# LED_Matrix.net
KiCad netlist of a schematic drawn in Altium Designer
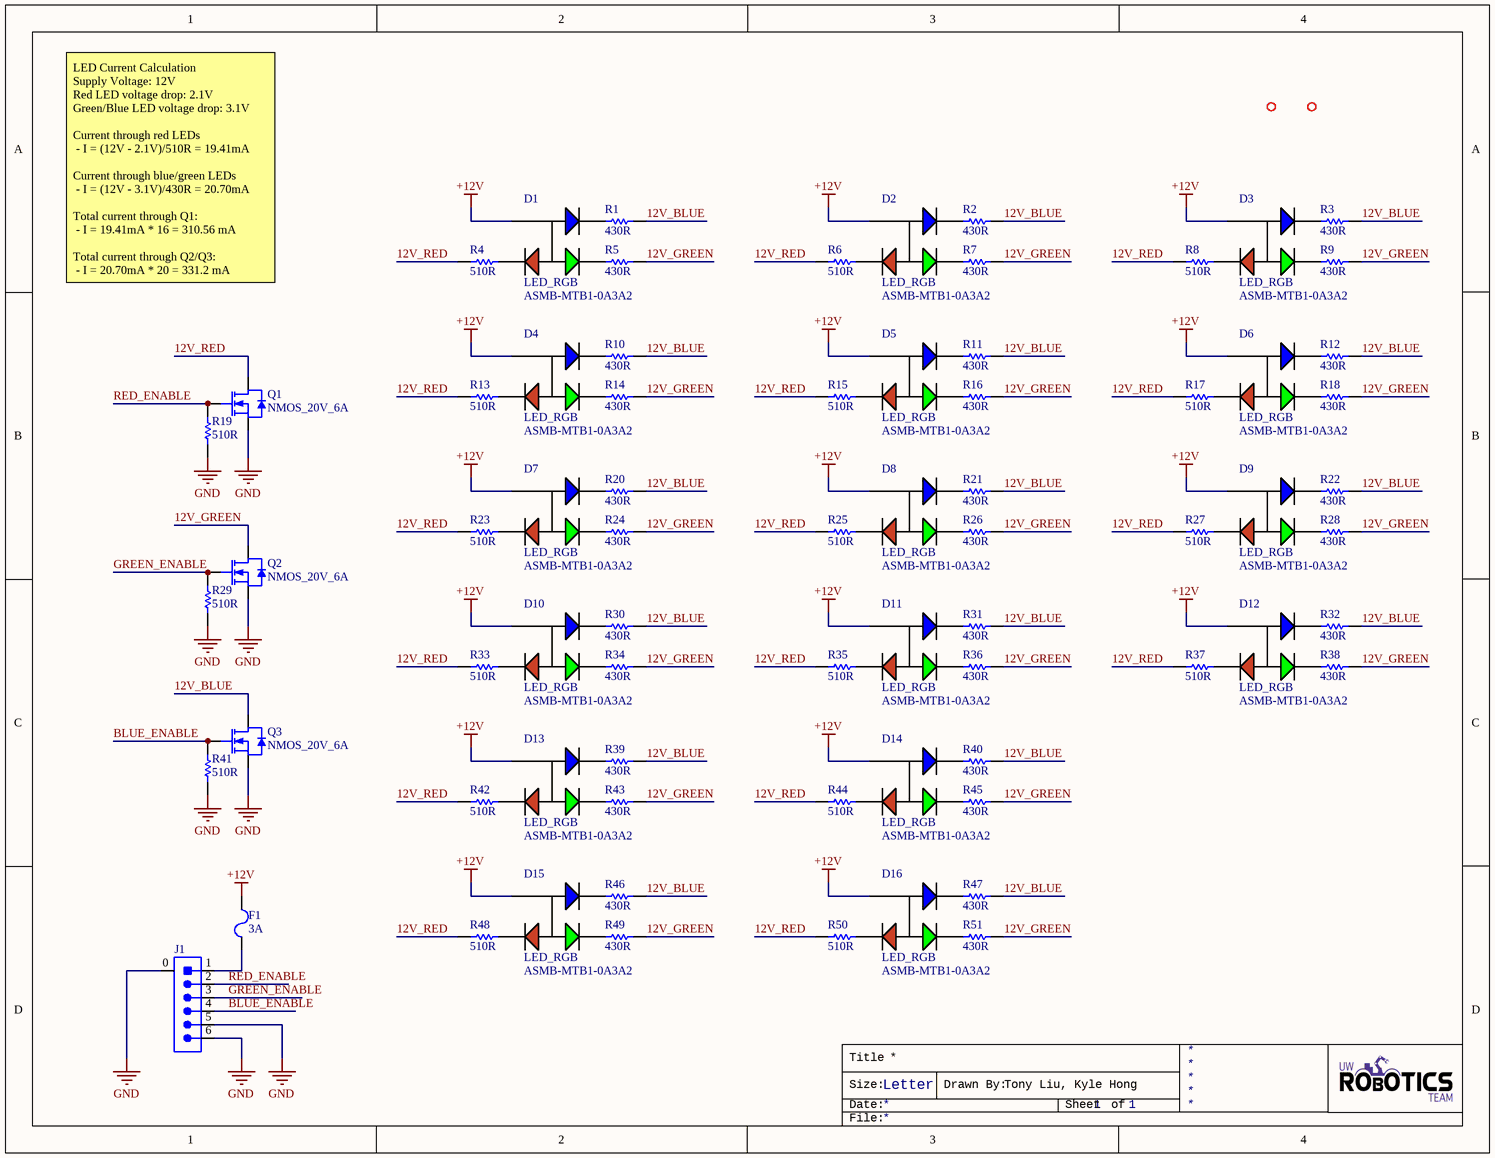
[diagram p0: LED Matrix.SchDoc]

(export (version "E")
  (design (tool "Eeschema 10.0.6"))
  (components
    (comp (ref "D1")
      (value "LED_RGB")
      (footprint "LED_RGB")
      (description "LED RGB DIFFUSED 4PLCC SMD")
      (fields (field (name "MANUFACTURER PART NUMBER 1") "ASMB-MTB1-0A3A2"))
      (libsource (lib "UWRT_Schematic_Library_2020") (part "LED_RGB"))
    )
    (comp (ref "D2")
      (value "LED_RGB")
      (footprint "LED_RGB")
      (description "LED RGB DIFFUSED 4PLCC SMD")
      (fields (field (name "MANUFACTURER PART NUMBER 1") "ASMB-MTB1-0A3A2"))
      (libsource (lib "UWRT_Schematic_Library_2020") (part "LED_RGB"))
    )
    (comp (ref "D3")
      (value "LED_RGB")
      (footprint "LED_RGB")
      (description "LED RGB DIFFUSED 4PLCC SMD")
      (fields (field (name "MANUFACTURER PART NUMBER 1") "ASMB-MTB1-0A3A2"))
      (libsource (lib "UWRT_Schematic_Library_2020") (part "LED_RGB"))
    )
    (comp (ref "D4")
      (value "LED_RGB")
      (footprint "LED_RGB")
      (description "LED RGB DIFFUSED 4PLCC SMD")
      (fields (field (name "MANUFACTURER PART NUMBER 1") "ASMB-MTB1-0A3A2"))
      (libsource (lib "UWRT_Schematic_Library_2020") (part "LED_RGB"))
    )
    (comp (ref "D5")
      (value "LED_RGB")
      (footprint "LED_RGB")
      (description "LED RGB DIFFUSED 4PLCC SMD")
      (fields (field (name "MANUFACTURER PART NUMBER 1") "ASMB-MTB1-0A3A2"))
      (libsource (lib "UWRT_Schematic_Library_2020") (part "LED_RGB"))
    )
    (comp (ref "D6")
      (value "LED_RGB")
      (footprint "LED_RGB")
      (description "LED RGB DIFFUSED 4PLCC SMD")
      (fields (field (name "MANUFACTURER PART NUMBER 1") "ASMB-MTB1-0A3A2"))
      (libsource (lib "UWRT_Schematic_Library_2020") (part "LED_RGB"))
    )
    (comp (ref "D7")
      (value "LED_RGB")
      (footprint "LED_RGB")
      (description "LED RGB DIFFUSED 4PLCC SMD")
      (fields (field (name "MANUFACTURER PART NUMBER 1") "ASMB-MTB1-0A3A2"))
      (libsource (lib "UWRT_Schematic_Library_2020") (part "LED_RGB"))
    )
    (comp (ref "D8")
      (value "LED_RGB")
      (footprint "LED_RGB")
      (description "LED RGB DIFFUSED 4PLCC SMD")
      (fields (field (name "MANUFACTURER PART NUMBER 1") "ASMB-MTB1-0A3A2"))
      (libsource (lib "UWRT_Schematic_Library_2020") (part "LED_RGB"))
    )
    (comp (ref "D9")
      (value "LED_RGB")
      (footprint "LED_RGB")
      (description "LED RGB DIFFUSED 4PLCC SMD")
      (fields (field (name "MANUFACTURER PART NUMBER 1") "ASMB-MTB1-0A3A2"))
      (libsource (lib "UWRT_Schematic_Library_2020") (part "LED_RGB"))
    )
    (comp (ref "D10")
      (value "LED_RGB")
      (footprint "LED_RGB")
      (description "LED RGB DIFFUSED 4PLCC SMD")
      (fields (field (name "MANUFACTURER PART NUMBER 1") "ASMB-MTB1-0A3A2"))
      (libsource (lib "UWRT_Schematic_Library_2020") (part "LED_RGB"))
    )
    (comp (ref "D11")
      (value "LED_RGB")
      (footprint "LED_RGB")
      (description "LED RGB DIFFUSED 4PLCC SMD")
      (fields (field (name "MANUFACTURER PART NUMBER 1") "ASMB-MTB1-0A3A2"))
      (libsource (lib "UWRT_Schematic_Library_2020") (part "LED_RGB"))
    )
    (comp (ref "D12")
      (value "LED_RGB")
      (footprint "LED_RGB")
      (description "LED RGB DIFFUSED 4PLCC SMD")
      (fields (field (name "MANUFACTURER PART NUMBER 1") "ASMB-MTB1-0A3A2"))
      (libsource (lib "UWRT_Schematic_Library_2020") (part "LED_RGB"))
    )
    (comp (ref "D13")
      (value "LED_RGB")
      (footprint "LED_RGB")
      (description "LED RGB DIFFUSED 4PLCC SMD")
      (fields (field (name "MANUFACTURER PART NUMBER 1") "ASMB-MTB1-0A3A2"))
      (libsource (lib "UWRT_Schematic_Library_2020") (part "LED_RGB"))
    )
    (comp (ref "D14")
      (value "LED_RGB")
      (footprint "LED_RGB")
      (description "LED RGB DIFFUSED 4PLCC SMD")
      (fields (field (name "MANUFACTURER PART NUMBER 1") "ASMB-MTB1-0A3A2"))
      (libsource (lib "UWRT_Schematic_Library_2020") (part "LED_RGB"))
    )
    (comp (ref "D15")
      (value "LED_RGB")
      (footprint "LED_RGB")
      (description "LED RGB DIFFUSED 4PLCC SMD")
      (fields (field (name "MANUFACTURER PART NUMBER 1") "ASMB-MTB1-0A3A2"))
      (libsource (lib "UWRT_Schematic_Library_2020") (part "LED_RGB"))
    )
    (comp (ref "D16")
      (value "LED_RGB")
      (footprint "LED_RGB")
      (description "LED RGB DIFFUSED 4PLCC SMD")
      (fields (field (name "MANUFACTURER PART NUMBER 1") "ASMB-MTB1-0A3A2"))
      (libsource (lib "UWRT_Schematic_Library_2020") (part "LED_RGB"))
    )
    (comp (ref "F1")
      (value "FUSE_3A_1206")
      (footprint "FUSE_1206")
      (description "FUSE BOARD MNT 3A 32VAC/VDC 1206")
      (fields (field (name "CURRENT RATING") "3A"))
      (libsource (lib "UWRT_Schematic_Library_2020") (part "FUSE_3A_1206"))
    )
    (comp (ref "J1")
      (value "CON_6M_SM_RA")
      (footprint "MOLEX-5024940670")
      (description "CONN HEADER SMD RIGHT ANGLE 2MM PITCH")
      (libsource (lib "UWRT_Schematic_Library_2020") (part "CON_6M_SM_RA"))
    )
    (comp (ref "MH1")
      (value "MOUNTING_HOLES")
      (footprint "MOUNTING_HOLE")
      (description "6cm x 6cm")
      (libsource (lib "UWRT_Schematic_Library_2020") (part "MOUNTING_HOLES"))
    )
    (comp (ref "MH2")
      (value "MOUNTING_HOLES")
      (footprint "MOUNTING_HOLE")
      (description "6cm x 6cm")
      (libsource (lib "UWRT_Schematic_Library_2020") (part "MOUNTING_HOLES"))
    )
    (comp (ref "Q1")
      (value "NMOS_20V_6A")
      (footprint "NMOS_SOT23-3")
      (description "MOSFET N-CH 20V 6A SOT23")
      (libsource (lib "UWRT_Schematic_Library_2020") (part "NMOS_20V_6A"))
    )
    (comp (ref "Q2")
      (value "NMOS_20V_6A")
      (footprint "NMOS_SOT23-3")
      (description "MOSFET N-CH 20V 6A SOT23")
      (libsource (lib "UWRT_Schematic_Library_2020") (part "NMOS_20V_6A"))
    )
    (comp (ref "Q3")
      (value "NMOS_20V_6A")
      (footprint "NMOS_SOT23-3")
      (description "MOSFET N-CH 20V 6A SOT23")
      (libsource (lib "UWRT_Schematic_Library_2020") (part "NMOS_20V_6A"))
    )
    (comp (ref "R1")
      (value "430R")
      (footprint "RESC2012X60N")
      (description "RES SMD 430 OHM 1% 1/8W 0805")
      (fields (field (name "TOLERANCE") "1%") (field (name "Comment") "RES_430R_0805"))
      (libsource (lib "UWRT_Schematic_Library_2020") (part "RES_430R_0805"))
    )
    (comp (ref "R2")
      (value "430R")
      (footprint "RESC2012X60N")
      (description "RES SMD 430 OHM 1% 1/8W 0805")
      (fields (field (name "TOLERANCE") "1%") (field (name "Comment") "RES_430R_0805"))
      (libsource (lib "UWRT_Schematic_Library_2020") (part "RES_430R_0805"))
    )
    (comp (ref "R3")
      (value "430R")
      (footprint "RESC2012X60N")
      (description "RES SMD 430 OHM 1% 1/8W 0805")
      (fields (field (name "TOLERANCE") "1%") (field (name "Comment") "RES_430R_0805"))
      (libsource (lib "UWRT_Schematic_Library_2020") (part "RES_430R_0805"))
    )
    (comp (ref "R4")
      (value "510R")
      (footprint "RESC2012X60N")
      (description "RES SMD 510 OHM 1% 1/8W 0805")
      (fields (field (name "TOLERANCE") "1%") (field (name "Comment") "RES_510R_0805"))
      (libsource (lib "UWRT_Schematic_Library_2020") (part "RES_510R_0805"))
    )
    (comp (ref "R5")
      (value "430R")
      (footprint "RESC2012X60N")
      (description "RES SMD 430 OHM 1% 1/8W 0805")
      (fields (field (name "TOLERANCE") "1%") (field (name "Comment") "RES_430R_0805"))
      (libsource (lib "UWRT_Schematic_Library_2020") (part "RES_430R_0805"))
    )
    (comp (ref "R6")
      (value "510R")
      (footprint "RESC2012X60N")
      (description "RES SMD 510 OHM 1% 1/8W 0805")
      (fields (field (name "TOLERANCE") "1%") (field (name "Comment") "RES_510R_0805"))
      (libsource (lib "UWRT_Schematic_Library_2020") (part "RES_510R_0805"))
    )
    (comp (ref "R7")
      (value "430R")
      (footprint "RESC2012X60N")
      (description "RES SMD 430 OHM 1% 1/8W 0805")
      (fields (field (name "TOLERANCE") "1%") (field (name "Comment") "RES_430R_0805"))
      (libsource (lib "UWRT_Schematic_Library_2020") (part "RES_430R_0805"))
    )
    (comp (ref "R8")
      (value "510R")
      (footprint "RESC2012X60N")
      (description "RES SMD 510 OHM 1% 1/8W 0805")
      (fields (field (name "TOLERANCE") "1%") (field (name "Comment") "RES_510R_0805"))
      (libsource (lib "UWRT_Schematic_Library_2020") (part "RES_510R_0805"))
    )
    (comp (ref "R9")
      (value "430R")
      (footprint "RESC2012X60N")
      (description "RES SMD 430 OHM 1% 1/8W 0805")
      (fields (field (name "TOLERANCE") "1%") (field (name "Comment") "RES_430R_0805"))
      (libsource (lib "UWRT_Schematic_Library_2020") (part "RES_430R_0805"))
    )
    (comp (ref "R10")
      (value "430R")
      (footprint "RESC2012X60N")
      (description "RES SMD 430 OHM 1% 1/8W 0805")
      (fields (field (name "TOLERANCE") "1%") (field (name "Comment") "RES_430R_0805"))
      (libsource (lib "UWRT_Schematic_Library_2020") (part "RES_430R_0805"))
    )
    (comp (ref "R11")
      (value "430R")
      (footprint "RESC2012X60N")
      (description "RES SMD 430 OHM 1% 1/8W 0805")
      (fields (field (name "TOLERANCE") "1%") (field (name "Comment") "RES_430R_0805"))
      (libsource (lib "UWRT_Schematic_Library_2020") (part "RES_430R_0805"))
    )
    (comp (ref "R12")
      (value "430R")
      (footprint "RESC2012X60N")
      (description "RES SMD 430 OHM 1% 1/8W 0805")
      (fields (field (name "TOLERANCE") "1%") (field (name "Comment") "RES_430R_0805"))
      (libsource (lib "UWRT_Schematic_Library_2020") (part "RES_430R_0805"))
    )
    (comp (ref "R13")
      (value "510R")
      (footprint "RESC2012X60N")
      (description "RES SMD 510 OHM 1% 1/8W 0805")
      (fields (field (name "TOLERANCE") "1%") (field (name "Comment") "RES_510R_0805"))
      (libsource (lib "UWRT_Schematic_Library_2020") (part "RES_510R_0805"))
    )
    (comp (ref "R14")
      (value "430R")
      (footprint "RESC2012X60N")
      (description "RES SMD 430 OHM 1% 1/8W 0805")
      (fields (field (name "TOLERANCE") "1%") (field (name "Comment") "RES_430R_0805"))
      (libsource (lib "UWRT_Schematic_Library_2020") (part "RES_430R_0805"))
    )
    (comp (ref "R15")
      (value "510R")
      (footprint "RESC2012X60N")
      (description "RES SMD 510 OHM 1% 1/8W 0805")
      (fields (field (name "TOLERANCE") "1%") (field (name "Comment") "RES_510R_0805"))
      (libsource (lib "UWRT_Schematic_Library_2020") (part "RES_510R_0805"))
    )
    (comp (ref "R16")
      (value "430R")
      (footprint "RESC2012X60N")
      (description "RES SMD 430 OHM 1% 1/8W 0805")
      (fields (field (name "TOLERANCE") "1%") (field (name "Comment") "RES_430R_0805"))
      (libsource (lib "UWRT_Schematic_Library_2020") (part "RES_430R_0805"))
    )
    (comp (ref "R17")
      (value "510R")
      (footprint "RESC2012X60N")
      (description "RES SMD 510 OHM 1% 1/8W 0805")
      (fields (field (name "TOLERANCE") "1%") (field (name "Comment") "RES_510R_0805"))
      (libsource (lib "UWRT_Schematic_Library_2020") (part "RES_510R_0805"))
    )
    (comp (ref "R18")
      (value "430R")
      (footprint "RESC2012X60N")
      (description "RES SMD 430 OHM 1% 1/8W 0805")
      (fields (field (name "TOLERANCE") "1%") (field (name "Comment") "RES_430R_0805"))
      (libsource (lib "UWRT_Schematic_Library_2020") (part "RES_430R_0805"))
    )
    (comp (ref "R19")
      (value "510R")
      (footprint "RESC2012X60N")
      (description "RES SMD 510 OHM 1% 1/8W 0805")
      (fields (field (name "TOLERANCE") "1%") (field (name "Comment") "RES_510R_0805"))
      (libsource (lib "UWRT_Schematic_Library_2020") (part "RES_510R_0805"))
    )
    (comp (ref "R20")
      (value "430R")
      (footprint "RESC2012X60N")
      (description "RES SMD 430 OHM 1% 1/8W 0805")
      (fields (field (name "TOLERANCE") "1%") (field (name "Comment") "RES_430R_0805"))
      (libsource (lib "UWRT_Schematic_Library_2020") (part "RES_430R_0805"))
    )
    (comp (ref "R21")
      (value "430R")
      (footprint "RESC2012X60N")
      (description "RES SMD 430 OHM 1% 1/8W 0805")
      (fields (field (name "TOLERANCE") "1%") (field (name "Comment") "RES_430R_0805"))
      (libsource (lib "UWRT_Schematic_Library_2020") (part "RES_430R_0805"))
    )
    (comp (ref "R22")
      (value "430R")
      (footprint "RESC2012X60N")
      (description "RES SMD 430 OHM 1% 1/8W 0805")
      (fields (field (name "TOLERANCE") "1%") (field (name "Comment") "RES_430R_0805"))
      (libsource (lib "UWRT_Schematic_Library_2020") (part "RES_430R_0805"))
    )
    (comp (ref "R23")
      (value "510R")
      (footprint "RESC2012X60N")
      (description "RES SMD 510 OHM 1% 1/8W 0805")
      (fields (field (name "TOLERANCE") "1%") (field (name "Comment") "RES_510R_0805"))
      (libsource (lib "UWRT_Schematic_Library_2020") (part "RES_510R_0805"))
    )
    (comp (ref "R24")
      (value "430R")
      (footprint "RESC2012X60N")
      (description "RES SMD 430 OHM 1% 1/8W 0805")
      (fields (field (name "TOLERANCE") "1%") (field (name "Comment") "RES_430R_0805"))
      (libsource (lib "UWRT_Schematic_Library_2020") (part "RES_430R_0805"))
    )
    (comp (ref "R25")
      (value "510R")
      (footprint "RESC2012X60N")
      (description "RES SMD 510 OHM 1% 1/8W 0805")
      (fields (field (name "TOLERANCE") "1%") (field (name "Comment") "RES_510R_0805"))
      (libsource (lib "UWRT_Schematic_Library_2020") (part "RES_510R_0805"))
    )
    (comp (ref "R26")
      (value "430R")
      (footprint "RESC2012X60N")
      (description "RES SMD 430 OHM 1% 1/8W 0805")
      (fields (field (name "TOLERANCE") "1%") (field (name "Comment") "RES_430R_0805"))
      (libsource (lib "UWRT_Schematic_Library_2020") (part "RES_430R_0805"))
    )
    (comp (ref "R27")
      (value "510R")
      (footprint "RESC2012X60N")
      (description "RES SMD 510 OHM 1% 1/8W 0805")
      (fields (field (name "TOLERANCE") "1%") (field (name "Comment") "RES_510R_0805"))
      (libsource (lib "UWRT_Schematic_Library_2020") (part "RES_510R_0805"))
    )
    (comp (ref "R28")
      (value "430R")
      (footprint "RESC2012X60N")
      (description "RES SMD 430 OHM 1% 1/8W 0805")
      (fields (field (name "TOLERANCE") "1%") (field (name "Comment") "RES_430R_0805"))
      (libsource (lib "UWRT_Schematic_Library_2020") (part "RES_430R_0805"))
    )
    (comp (ref "R29")
      (value "510R")
      (footprint "RESC2012X60N")
      (description "RES SMD 510 OHM 1% 1/8W 0805")
      (fields (field (name "TOLERANCE") "1%") (field (name "Comment") "RES_510R_0805"))
      (libsource (lib "UWRT_Schematic_Library_2020") (part "RES_510R_0805"))
    )
    (comp (ref "R30")
      (value "430R")
      (footprint "RESC2012X60N")
      (description "RES SMD 430 OHM 1% 1/8W 0805")
      (fields (field (name "TOLERANCE") "1%") (field (name "Comment") "RES_430R_0805"))
      (libsource (lib "UWRT_Schematic_Library_2020") (part "RES_430R_0805"))
    )
    (comp (ref "R31")
      (value "430R")
      (footprint "RESC2012X60N")
      (description "RES SMD 430 OHM 1% 1/8W 0805")
      (fields (field (name "TOLERANCE") "1%") (field (name "Comment") "RES_430R_0805"))
      (libsource (lib "UWRT_Schematic_Library_2020") (part "RES_430R_0805"))
    )
    (comp (ref "R32")
      (value "430R")
      (footprint "RESC2012X60N")
      (description "RES SMD 430 OHM 1% 1/8W 0805")
      (fields (field (name "TOLERANCE") "1%") (field (name "Comment") "RES_430R_0805"))
      (libsource (lib "UWRT_Schematic_Library_2020") (part "RES_430R_0805"))
    )
    (comp (ref "R33")
      (value "510R")
      (footprint "RESC2012X60N")
      (description "RES SMD 510 OHM 1% 1/8W 0805")
      (fields (field (name "TOLERANCE") "1%") (field (name "Comment") "RES_510R_0805"))
      (libsource (lib "UWRT_Schematic_Library_2020") (part "RES_510R_0805"))
    )
    (comp (ref "R34")
      (value "430R")
      (footprint "RESC2012X60N")
      (description "RES SMD 430 OHM 1% 1/8W 0805")
      (fields (field (name "TOLERANCE") "1%") (field (name "Comment") "RES_430R_0805"))
      (libsource (lib "UWRT_Schematic_Library_2020") (part "RES_430R_0805"))
    )
    (comp (ref "R35")
      (value "510R")
      (footprint "RESC2012X60N")
      (description "RES SMD 510 OHM 1% 1/8W 0805")
      (fields (field (name "TOLERANCE") "1%") (field (name "Comment") "RES_510R_0805"))
      (libsource (lib "UWRT_Schematic_Library_2020") (part "RES_510R_0805"))
    )
    (comp (ref "R36")
      (value "430R")
      (footprint "RESC2012X60N")
      (description "RES SMD 430 OHM 1% 1/8W 0805")
      (fields (field (name "TOLERANCE") "1%") (field (name "Comment") "RES_430R_0805"))
      (libsource (lib "UWRT_Schematic_Library_2020") (part "RES_430R_0805"))
    )
    (comp (ref "R37")
      (value "510R")
      (footprint "RESC2012X60N")
      (description "RES SMD 510 OHM 1% 1/8W 0805")
      (fields (field (name "TOLERANCE") "1%") (field (name "Comment") "RES_510R_0805"))
      (libsource (lib "UWRT_Schematic_Library_2020") (part "RES_510R_0805"))
    )
    (comp (ref "R38")
      (value "430R")
      (footprint "RESC2012X60N")
      (description "RES SMD 430 OHM 1% 1/8W 0805")
      (fields (field (name "TOLERANCE") "1%") (field (name "Comment") "RES_430R_0805"))
      (libsource (lib "UWRT_Schematic_Library_2020") (part "RES_430R_0805"))
    )
    (comp (ref "R39")
      (value "430R")
      (footprint "RESC2012X60N")
      (description "RES SMD 430 OHM 1% 1/8W 0805")
      (fields (field (name "TOLERANCE") "1%") (field (name "Comment") "RES_430R_0805"))
      (libsource (lib "UWRT_Schematic_Library_2020") (part "RES_430R_0805"))
    )
    (comp (ref "R40")
      (value "430R")
      (footprint "RESC2012X60N")
      (description "RES SMD 430 OHM 1% 1/8W 0805")
      (fields (field (name "TOLERANCE") "1%") (field (name "Comment") "RES_430R_0805"))
      (libsource (lib "UWRT_Schematic_Library_2020") (part "RES_430R_0805"))
    )
    (comp (ref "R41")
      (value "510R")
      (footprint "RESC2012X60N")
      (description "RES SMD 510 OHM 1% 1/8W 0805")
      (fields (field (name "TOLERANCE") "1%") (field (name "Comment") "RES_510R_0805"))
      (libsource (lib "UWRT_Schematic_Library_2020") (part "RES_510R_0805"))
    )
    (comp (ref "R42")
      (value "510R")
      (footprint "RESC2012X60N")
      (description "RES SMD 510 OHM 1% 1/8W 0805")
      (fields (field (name "TOLERANCE") "1%") (field (name "Comment") "RES_510R_0805"))
      (libsource (lib "UWRT_Schematic_Library_2020") (part "RES_510R_0805"))
    )
    (comp (ref "R43")
      (value "430R")
      (footprint "RESC2012X60N")
      (description "RES SMD 430 OHM 1% 1/8W 0805")
      (fields (field (name "TOLERANCE") "1%") (field (name "Comment") "RES_430R_0805"))
      (libsource (lib "UWRT_Schematic_Library_2020") (part "RES_430R_0805"))
    )
    (comp (ref "R44")
      (value "510R")
      (footprint "RESC2012X60N")
      (description "RES SMD 510 OHM 1% 1/8W 0805")
      (fields (field (name "TOLERANCE") "1%") (field (name "Comment") "RES_510R_0805"))
      (libsource (lib "UWRT_Schematic_Library_2020") (part "RES_510R_0805"))
    )
    (comp (ref "R45")
      (value "430R")
      (footprint "RESC2012X60N")
      (description "RES SMD 430 OHM 1% 1/8W 0805")
      (fields (field (name "TOLERANCE") "1%") (field (name "Comment") "RES_430R_0805"))
      (libsource (lib "UWRT_Schematic_Library_2020") (part "RES_430R_0805"))
    )
    (comp (ref "R46")
      (value "430R")
      (footprint "RESC2012X60N")
      (description "RES SMD 430 OHM 1% 1/8W 0805")
      (fields (field (name "TOLERANCE") "1%") (field (name "Comment") "RES_430R_0805"))
      (libsource (lib "UWRT_Schematic_Library_2020") (part "RES_430R_0805"))
    )
    (comp (ref "R47")
      (value "430R")
      (footprint "RESC2012X60N")
      (description "RES SMD 430 OHM 1% 1/8W 0805")
      (fields (field (name "TOLERANCE") "1%") (field (name "Comment") "RES_430R_0805"))
      (libsource (lib "UWRT_Schematic_Library_2020") (part "RES_430R_0805"))
    )
    (comp (ref "R48")
      (value "510R")
      (footprint "RESC2012X60N")
      (description "RES SMD 510 OHM 1% 1/8W 0805")
      (fields (field (name "TOLERANCE") "1%") (field (name "Comment") "RES_510R_0805"))
      (libsource (lib "UWRT_Schematic_Library_2020") (part "RES_510R_0805"))
    )
    (comp (ref "R49")
      (value "430R")
      (footprint "RESC2012X60N")
      (description "RES SMD 430 OHM 1% 1/8W 0805")
      (fields (field (name "TOLERANCE") "1%") (field (name "Comment") "RES_430R_0805"))
      (libsource (lib "UWRT_Schematic_Library_2020") (part "RES_430R_0805"))
    )
    (comp (ref "R50")
      (value "510R")
      (footprint "RESC2012X60N")
      (description "RES SMD 510 OHM 1% 1/8W 0805")
      (fields (field (name "TOLERANCE") "1%") (field (name "Comment") "RES_510R_0805"))
      (libsource (lib "UWRT_Schematic_Library_2020") (part "RES_510R_0805"))
    )
    (comp (ref "R51")
      (value "430R")
      (footprint "RESC2012X60N")
      (description "RES SMD 430 OHM 1% 1/8W 0805")
      (fields (field (name "TOLERANCE") "1%") (field (name "Comment") "RES_430R_0805"))
      (libsource (lib "UWRT_Schematic_Library_2020") (part "RES_430R_0805"))
    )
  )
  (nets
    (net (code "1") (name "+12V") (class "Default")
      (node (ref "D1") (pin "4") (pinfunction "9_4") (pintype "passive"))
      (node (ref "D10") (pin "4") (pinfunction "9_4") (pintype "passive"))
      (node (ref "D11") (pin "4") (pinfunction "9_4") (pintype "passive"))
      (node (ref "D12") (pin "4") (pinfunction "9_4") (pintype "passive"))
      (node (ref "D13") (pin "4") (pinfunction "9_4") (pintype "passive"))
      (node (ref "D14") (pin "4") (pinfunction "9_4") (pintype "passive"))
      (node (ref "D15") (pin "4") (pinfunction "9_4") (pintype "passive"))
      (node (ref "D16") (pin "4") (pinfunction "9_4") (pintype "passive"))
      (node (ref "D2") (pin "4") (pinfunction "9_4") (pintype "passive"))
      (node (ref "D3") (pin "4") (pinfunction "9_4") (pintype "passive"))
      (node (ref "D4") (pin "4") (pinfunction "9_4") (pintype "passive"))
      (node (ref "D5") (pin "4") (pinfunction "9_4") (pintype "passive"))
      (node (ref "D6") (pin "4") (pinfunction "9_4") (pintype "passive"))
      (node (ref "D7") (pin "4") (pinfunction "9_4") (pintype "passive"))
      (node (ref "D8") (pin "4") (pinfunction "9_4") (pintype "passive"))
      (node (ref "D9") (pin "4") (pinfunction "9_4") (pintype "passive"))
      (node (ref "F1") (pin "2") (pinfunction "2_2") (pintype "passive"))
    )
    (net (code "2") (name "/12V_BLUE") (class "Default")
      (node (ref "Q3") (pin "3") (pinfunction "D_3") (pintype "passive"))
      (node (ref "R1") (pin "1") (pinfunction "1_1") (pintype "passive"))
      (node (ref "R10") (pin "1") (pinfunction "1_1") (pintype "passive"))
      (node (ref "R11") (pin "1") (pinfunction "1_1") (pintype "passive"))
      (node (ref "R12") (pin "1") (pinfunction "1_1") (pintype "passive"))
      (node (ref "R2") (pin "1") (pinfunction "1_1") (pintype "passive"))
      (node (ref "R20") (pin "1") (pinfunction "1_1") (pintype "passive"))
      (node (ref "R21") (pin "1") (pinfunction "1_1") (pintype "passive"))
      (node (ref "R22") (pin "1") (pinfunction "1_1") (pintype "passive"))
      (node (ref "R3") (pin "1") (pinfunction "1_1") (pintype "passive"))
      (node (ref "R30") (pin "1") (pinfunction "1_1") (pintype "passive"))
      (node (ref "R31") (pin "1") (pinfunction "1_1") (pintype "passive"))
      (node (ref "R32") (pin "1") (pinfunction "1_1") (pintype "passive"))
      (node (ref "R39") (pin "1") (pinfunction "1_1") (pintype "passive"))
      (node (ref "R40") (pin "1") (pinfunction "1_1") (pintype "passive"))
      (node (ref "R46") (pin "1") (pinfunction "1_1") (pintype "passive"))
      (node (ref "R47") (pin "1") (pinfunction "1_1") (pintype "passive"))
    )
    (net (code "3") (name "/12V_GREEN") (class "Default")
      (node (ref "Q2") (pin "3") (pinfunction "D_3") (pintype "passive"))
      (node (ref "R14") (pin "1") (pinfunction "1_1") (pintype "passive"))
      (node (ref "R16") (pin "1") (pinfunction "1_1") (pintype "passive"))
      (node (ref "R18") (pin "1") (pinfunction "1_1") (pintype "passive"))
      (node (ref "R24") (pin "1") (pinfunction "1_1") (pintype "passive"))
      (node (ref "R26") (pin "1") (pinfunction "1_1") (pintype "passive"))
      (node (ref "R28") (pin "1") (pinfunction "1_1") (pintype "passive"))
      (node (ref "R34") (pin "1") (pinfunction "1_1") (pintype "passive"))
      (node (ref "R36") (pin "1") (pinfunction "1_1") (pintype "passive"))
      (node (ref "R38") (pin "1") (pinfunction "1_1") (pintype "passive"))
      (node (ref "R43") (pin "1") (pinfunction "1_1") (pintype "passive"))
      (node (ref "R45") (pin "1") (pinfunction "1_1") (pintype "passive"))
      (node (ref "R49") (pin "1") (pinfunction "1_1") (pintype "passive"))
      (node (ref "R5") (pin "1") (pinfunction "1_1") (pintype "passive"))
      (node (ref "R51") (pin "1") (pinfunction "1_1") (pintype "passive"))
      (node (ref "R7") (pin "1") (pinfunction "1_1") (pintype "passive"))
      (node (ref "R9") (pin "1") (pinfunction "1_1") (pintype "passive"))
    )
    (net (code "4") (name "/12V_RED") (class "Default")
      (node (ref "Q1") (pin "3") (pinfunction "D_3") (pintype "passive"))
      (node (ref "R13") (pin "2") (pinfunction "2_2") (pintype "passive"))
      (node (ref "R15") (pin "2") (pinfunction "2_2") (pintype "passive"))
      (node (ref "R17") (pin "2") (pinfunction "2_2") (pintype "passive"))
      (node (ref "R23") (pin "2") (pinfunction "2_2") (pintype "passive"))
      (node (ref "R25") (pin "2") (pinfunction "2_2") (pintype "passive"))
      (node (ref "R27") (pin "2") (pinfunction "2_2") (pintype "passive"))
      (node (ref "R33") (pin "2") (pinfunction "2_2") (pintype "passive"))
      (node (ref "R35") (pin "2") (pinfunction "2_2") (pintype "passive"))
      (node (ref "R37") (pin "2") (pinfunction "2_2") (pintype "passive"))
      (node (ref "R4") (pin "2") (pinfunction "2_2") (pintype "passive"))
      (node (ref "R42") (pin "2") (pinfunction "2_2") (pintype "passive"))
      (node (ref "R44") (pin "2") (pinfunction "2_2") (pintype "passive"))
      (node (ref "R48") (pin "2") (pinfunction "2_2") (pintype "passive"))
      (node (ref "R50") (pin "2") (pinfunction "2_2") (pintype "passive"))
      (node (ref "R6") (pin "2") (pinfunction "2_2") (pintype "passive"))
      (node (ref "R8") (pin "2") (pinfunction "2_2") (pintype "passive"))
    )
    (net (code "5") (name "/BLUE_ENABLE") (class "Default")
      (node (ref "J1") (pin "4") (pinfunction "4_4") (pintype "passive"))
      (node (ref "Q3") (pin "1") (pinfunction "G_1") (pintype "passive"))
      (node (ref "R41") (pin "2") (pinfunction "2_2") (pintype "passive"))
    )
    (net (code "6") (name "/GREEN_ENABLE") (class "Default")
      (node (ref "J1") (pin "3") (pinfunction "3_3") (pintype "passive"))
      (node (ref "Q2") (pin "1") (pinfunction "G_1") (pintype "passive"))
      (node (ref "R29") (pin "2") (pinfunction "2_2") (pintype "passive"))
    )
    (net (code "7") (name "/RED_ENABLE") (class "Default")
      (node (ref "J1") (pin "2") (pinfunction "2_2") (pintype "passive"))
      (node (ref "Q1") (pin "1") (pinfunction "G_1") (pintype "passive"))
      (node (ref "R19") (pin "2") (pinfunction "2_2") (pintype "passive"))
    )
    (net (code "8") (name "GND") (class "Default")
      (node (ref "J1") (pin "0") (pinfunction "0_0") (pintype "passive"))
      (node (ref "J1") (pin "5") (pinfunction "5_5") (pintype "passive"))
      (node (ref "J1") (pin "6") (pinfunction "6_6") (pintype "passive"))
      (node (ref "Q1") (pin "2") (pinfunction "S_2") (pintype "passive"))
      (node (ref "Q2") (pin "2") (pinfunction "S_2") (pintype "passive"))
      (node (ref "Q3") (pin "2") (pinfunction "S_2") (pintype "passive"))
      (node (ref "R19") (pin "1") (pinfunction "1_1") (pintype "passive"))
      (node (ref "R29") (pin "1") (pinfunction "1_1") (pintype "passive"))
      (node (ref "R41") (pin "1") (pinfunction "1_1") (pintype "passive"))
    )
    (net (code "9") (name "Net-(D1-10)") (class "Default")
      (node (ref "D1") (pin "3") (pinfunction "10_3") (pintype "passive"))
      (node (ref "R1") (pin "2") (pinfunction "2_2") (pintype "passive"))
    )
    (net (code "10") (name "Net-(D1-11)") (class "Default")
      (node (ref "D1") (pin "1") (pinfunction "11_1") (pintype "passive"))
      (node (ref "R4") (pin "1") (pinfunction "1_1") (pintype "passive"))
    )
    (net (code "11") (name "Net-(D1-12)") (class "Default")
      (node (ref "D1") (pin "2") (pinfunction "12_2") (pintype "passive"))
      (node (ref "R5") (pin "2") (pinfunction "2_2") (pintype "passive"))
    )
    (net (code "12") (name "Net-(D2-10)") (class "Default")
      (node (ref "D2") (pin "3") (pinfunction "10_3") (pintype "passive"))
      (node (ref "R2") (pin "2") (pinfunction "2_2") (pintype "passive"))
    )
    (net (code "13") (name "Net-(D2-11)") (class "Default")
      (node (ref "D2") (pin "1") (pinfunction "11_1") (pintype "passive"))
      (node (ref "R6") (pin "1") (pinfunction "1_1") (pintype "passive"))
    )
    (net (code "14") (name "Net-(D2-12)") (class "Default")
      (node (ref "D2") (pin "2") (pinfunction "12_2") (pintype "passive"))
      (node (ref "R7") (pin "2") (pinfunction "2_2") (pintype "passive"))
    )
    (net (code "15") (name "Net-(D3-10)") (class "Default")
      (node (ref "D3") (pin "3") (pinfunction "10_3") (pintype "passive"))
      (node (ref "R3") (pin "2") (pinfunction "2_2") (pintype "passive"))
    )
    (net (code "16") (name "Net-(D3-11)") (class "Default")
      (node (ref "D3") (pin "1") (pinfunction "11_1") (pintype "passive"))
      (node (ref "R8") (pin "1") (pinfunction "1_1") (pintype "passive"))
    )
    (net (code "17") (name "Net-(D3-12)") (class "Default")
      (node (ref "D3") (pin "2") (pinfunction "12_2") (pintype "passive"))
      (node (ref "R9") (pin "2") (pinfunction "2_2") (pintype "passive"))
    )
    (net (code "18") (name "Net-(D4-10)") (class "Default")
      (node (ref "D4") (pin "3") (pinfunction "10_3") (pintype "passive"))
      (node (ref "R10") (pin "2") (pinfunction "2_2") (pintype "passive"))
    )
    (net (code "19") (name "Net-(D4-11)") (class "Default")
      (node (ref "D4") (pin "1") (pinfunction "11_1") (pintype "passive"))
      (node (ref "R13") (pin "1") (pinfunction "1_1") (pintype "passive"))
    )
    (net (code "20") (name "Net-(D4-12)") (class "Default")
      (node (ref "D4") (pin "2") (pinfunction "12_2") (pintype "passive"))
      (node (ref "R14") (pin "2") (pinfunction "2_2") (pintype "passive"))
    )
    (net (code "21") (name "Net-(D5-10)") (class "Default")
      (node (ref "D5") (pin "3") (pinfunction "10_3") (pintype "passive"))
      (node (ref "R11") (pin "2") (pinfunction "2_2") (pintype "passive"))
    )
    (net (code "22") (name "Net-(D5-11)") (class "Default")
      (node (ref "D5") (pin "1") (pinfunction "11_1") (pintype "passive"))
      (node (ref "R15") (pin "1") (pinfunction "1_1") (pintype "passive"))
    )
    (net (code "23") (name "Net-(D5-12)") (class "Default")
      (node (ref "D5") (pin "2") (pinfunction "12_2") (pintype "passive"))
      (node (ref "R16") (pin "2") (pinfunction "2_2") (pintype "passive"))
    )
    (net (code "24") (name "Net-(D6-10)") (class "Default")
      (node (ref "D6") (pin "3") (pinfunction "10_3") (pintype "passive"))
      (node (ref "R12") (pin "2") (pinfunction "2_2") (pintype "passive"))
    )
    (net (code "25") (name "Net-(D6-11)") (class "Default")
      (node (ref "D6") (pin "1") (pinfunction "11_1") (pintype "passive"))
      (node (ref "R17") (pin "1") (pinfunction "1_1") (pintype "passive"))
    )
    (net (code "26") (name "Net-(D6-12)") (class "Default")
      (node (ref "D6") (pin "2") (pinfunction "12_2") (pintype "passive"))
      (node (ref "R18") (pin "2") (pinfunction "2_2") (pintype "passive"))
    )
    (net (code "27") (name "Net-(D7-10)") (class "Default")
      (node (ref "D7") (pin "3") (pinfunction "10_3") (pintype "passive"))
      (node (ref "R20") (pin "2") (pinfunction "2_2") (pintype "passive"))
    )
    (net (code "28") (name "Net-(D7-11)") (class "Default")
      (node (ref "D7") (pin "1") (pinfunction "11_1") (pintype "passive"))
      (node (ref "R23") (pin "1") (pinfunction "1_1") (pintype "passive"))
    )
    (net (code "29") (name "Net-(D7-12)") (class "Default")
      (node (ref "D7") (pin "2") (pinfunction "12_2") (pintype "passive"))
      (node (ref "R24") (pin "2") (pinfunction "2_2") (pintype "passive"))
    )
    (net (code "30") (name "Net-(D8-10)") (class "Default")
      (node (ref "D8") (pin "3") (pinfunction "10_3") (pintype "passive"))
      (node (ref "R21") (pin "2") (pinfunction "2_2") (pintype "passive"))
    )
    (net (code "31") (name "Net-(D8-11)") (class "Default")
      (node (ref "D8") (pin "1") (pinfunction "11_1") (pintype "passive"))
      (node (ref "R25") (pin "1") (pinfunction "1_1") (pintype "passive"))
    )
    (net (code "32") (name "Net-(D8-12)") (class "Default")
      (node (ref "D8") (pin "2") (pinfunction "12_2") (pintype "passive"))
      (node (ref "R26") (pin "2") (pinfunction "2_2") (pintype "passive"))
    )
    (net (code "33") (name "Net-(D9-10)") (class "Default")
      (node (ref "D9") (pin "3") (pinfunction "10_3") (pintype "passive"))
      (node (ref "R22") (pin "2") (pinfunction "2_2") (pintype "passive"))
    )
    (net (code "34") (name "Net-(D9-11)") (class "Default")
      (node (ref "D9") (pin "1") (pinfunction "11_1") (pintype "passive"))
      (node (ref "R27") (pin "1") (pinfunction "1_1") (pintype "passive"))
    )
    (net (code "35") (name "Net-(D9-12)") (class "Default")
      (node (ref "D9") (pin "2") (pinfunction "12_2") (pintype "passive"))
      (node (ref "R28") (pin "2") (pinfunction "2_2") (pintype "passive"))
    )
    (net (code "36") (name "Net-(D10-10)") (class "Default")
      (node (ref "D10") (pin "3") (pinfunction "10_3") (pintype "passive"))
      (node (ref "R30") (pin "2") (pinfunction "2_2") (pintype "passive"))
    )
    (net (code "37") (name "Net-(D10-11)") (class "Default")
      (node (ref "D10") (pin "1") (pinfunction "11_1") (pintype "passive"))
      (node (ref "R33") (pin "1") (pinfunction "1_1") (pintype "passive"))
    )
    (net (code "38") (name "Net-(D10-12)") (class "Default")
      (node (ref "D10") (pin "2") (pinfunction "12_2") (pintype "passive"))
      (node (ref "R34") (pin "2") (pinfunction "2_2") (pintype "passive"))
    )
    (net (code "39") (name "Net-(D11-10)") (class "Default")
      (node (ref "D11") (pin "3") (pinfunction "10_3") (pintype "passive"))
      (node (ref "R31") (pin "2") (pinfunction "2_2") (pintype "passive"))
    )
    (net (code "40") (name "Net-(D11-11)") (class "Default")
      (node (ref "D11") (pin "1") (pinfunction "11_1") (pintype "passive"))
      (node (ref "R35") (pin "1") (pinfunction "1_1") (pintype "passive"))
    )
    (net (code "41") (name "Net-(D11-12)") (class "Default")
      (node (ref "D11") (pin "2") (pinfunction "12_2") (pintype "passive"))
      (node (ref "R36") (pin "2") (pinfunction "2_2") (pintype "passive"))
    )
    (net (code "42") (name "Net-(D12-10)") (class "Default")
      (node (ref "D12") (pin "3") (pinfunction "10_3") (pintype "passive"))
      (node (ref "R32") (pin "2") (pinfunction "2_2") (pintype "passive"))
    )
    (net (code "43") (name "Net-(D12-11)") (class "Default")
      (node (ref "D12") (pin "1") (pinfunction "11_1") (pintype "passive"))
      (node (ref "R37") (pin "1") (pinfunction "1_1") (pintype "passive"))
    )
    (net (code "44") (name "Net-(D12-12)") (class "Default")
      (node (ref "D12") (pin "2") (pinfunction "12_2") (pintype "passive"))
      (node (ref "R38") (pin "2") (pinfunction "2_2") (pintype "passive"))
    )
    (net (code "45") (name "Net-(D13-10)") (class "Default")
      (node (ref "D13") (pin "3") (pinfunction "10_3") (pintype "passive"))
      (node (ref "R39") (pin "2") (pinfunction "2_2") (pintype "passive"))
    )
    (net (code "46") (name "Net-(D13-11)") (class "Default")
      (node (ref "D13") (pin "1") (pinfunction "11_1") (pintype "passive"))
      (node (ref "R42") (pin "1") (pinfunction "1_1") (pintype "passive"))
    )
    (net (code "47") (name "Net-(D13-12)") (class "Default")
      (node (ref "D13") (pin "2") (pinfunction "12_2") (pintype "passive"))
      (node (ref "R43") (pin "2") (pinfunction "2_2") (pintype "passive"))
    )
    (net (code "48") (name "Net-(D14-10)") (class "Default")
      (node (ref "D14") (pin "3") (pinfunction "10_3") (pintype "passive"))
      (node (ref "R40") (pin "2") (pinfunction "2_2") (pintype "passive"))
    )
    (net (code "49") (name "Net-(D14-11)") (class "Default")
      (node (ref "D14") (pin "1") (pinfunction "11_1") (pintype "passive"))
      (node (ref "R44") (pin "1") (pinfunction "1_1") (pintype "passive"))
    )
    (net (code "50") (name "Net-(D14-12)") (class "Default")
      (node (ref "D14") (pin "2") (pinfunction "12_2") (pintype "passive"))
      (node (ref "R45") (pin "2") (pinfunction "2_2") (pintype "passive"))
    )
    (net (code "51") (name "Net-(D15-10)") (class "Default")
      (node (ref "D15") (pin "3") (pinfunction "10_3") (pintype "passive"))
      (node (ref "R46") (pin "2") (pinfunction "2_2") (pintype "passive"))
    )
    (net (code "52") (name "Net-(D15-11)") (class "Default")
      (node (ref "D15") (pin "1") (pinfunction "11_1") (pintype "passive"))
      (node (ref "R48") (pin "1") (pinfunction "1_1") (pintype "passive"))
    )
    (net (code "53") (name "Net-(D15-12)") (class "Default")
      (node (ref "D15") (pin "2") (pinfunction "12_2") (pintype "passive"))
      (node (ref "R49") (pin "2") (pinfunction "2_2") (pintype "passive"))
    )
    (net (code "54") (name "Net-(D16-10)") (class "Default")
      (node (ref "D16") (pin "3") (pinfunction "10_3") (pintype "passive"))
      (node (ref "R47") (pin "2") (pinfunction "2_2") (pintype "passive"))
    )
    (net (code "55") (name "Net-(D16-11)") (class "Default")
      (node (ref "D16") (pin "1") (pinfunction "11_1") (pintype "passive"))
      (node (ref "R50") (pin "1") (pinfunction "1_1") (pintype "passive"))
    )
    (net (code "56") (name "Net-(D16-12)") (class "Default")
      (node (ref "D16") (pin "2") (pinfunction "12_2") (pintype "passive"))
      (node (ref "R51") (pin "2") (pinfunction "2_2") (pintype "passive"))
    )
    (net (code "57") (name "Net-(F1-Pad1)") (class "Default")
      (node (ref "F1") (pin "1") (pinfunction "1_1") (pintype "passive"))
      (node (ref "J1") (pin "1") (pinfunction "1_1") (pintype "passive"))
    )
  )
)
